# MR26_GSS_8.net
KiCad netlist of a schematic drawn in Altium Designer
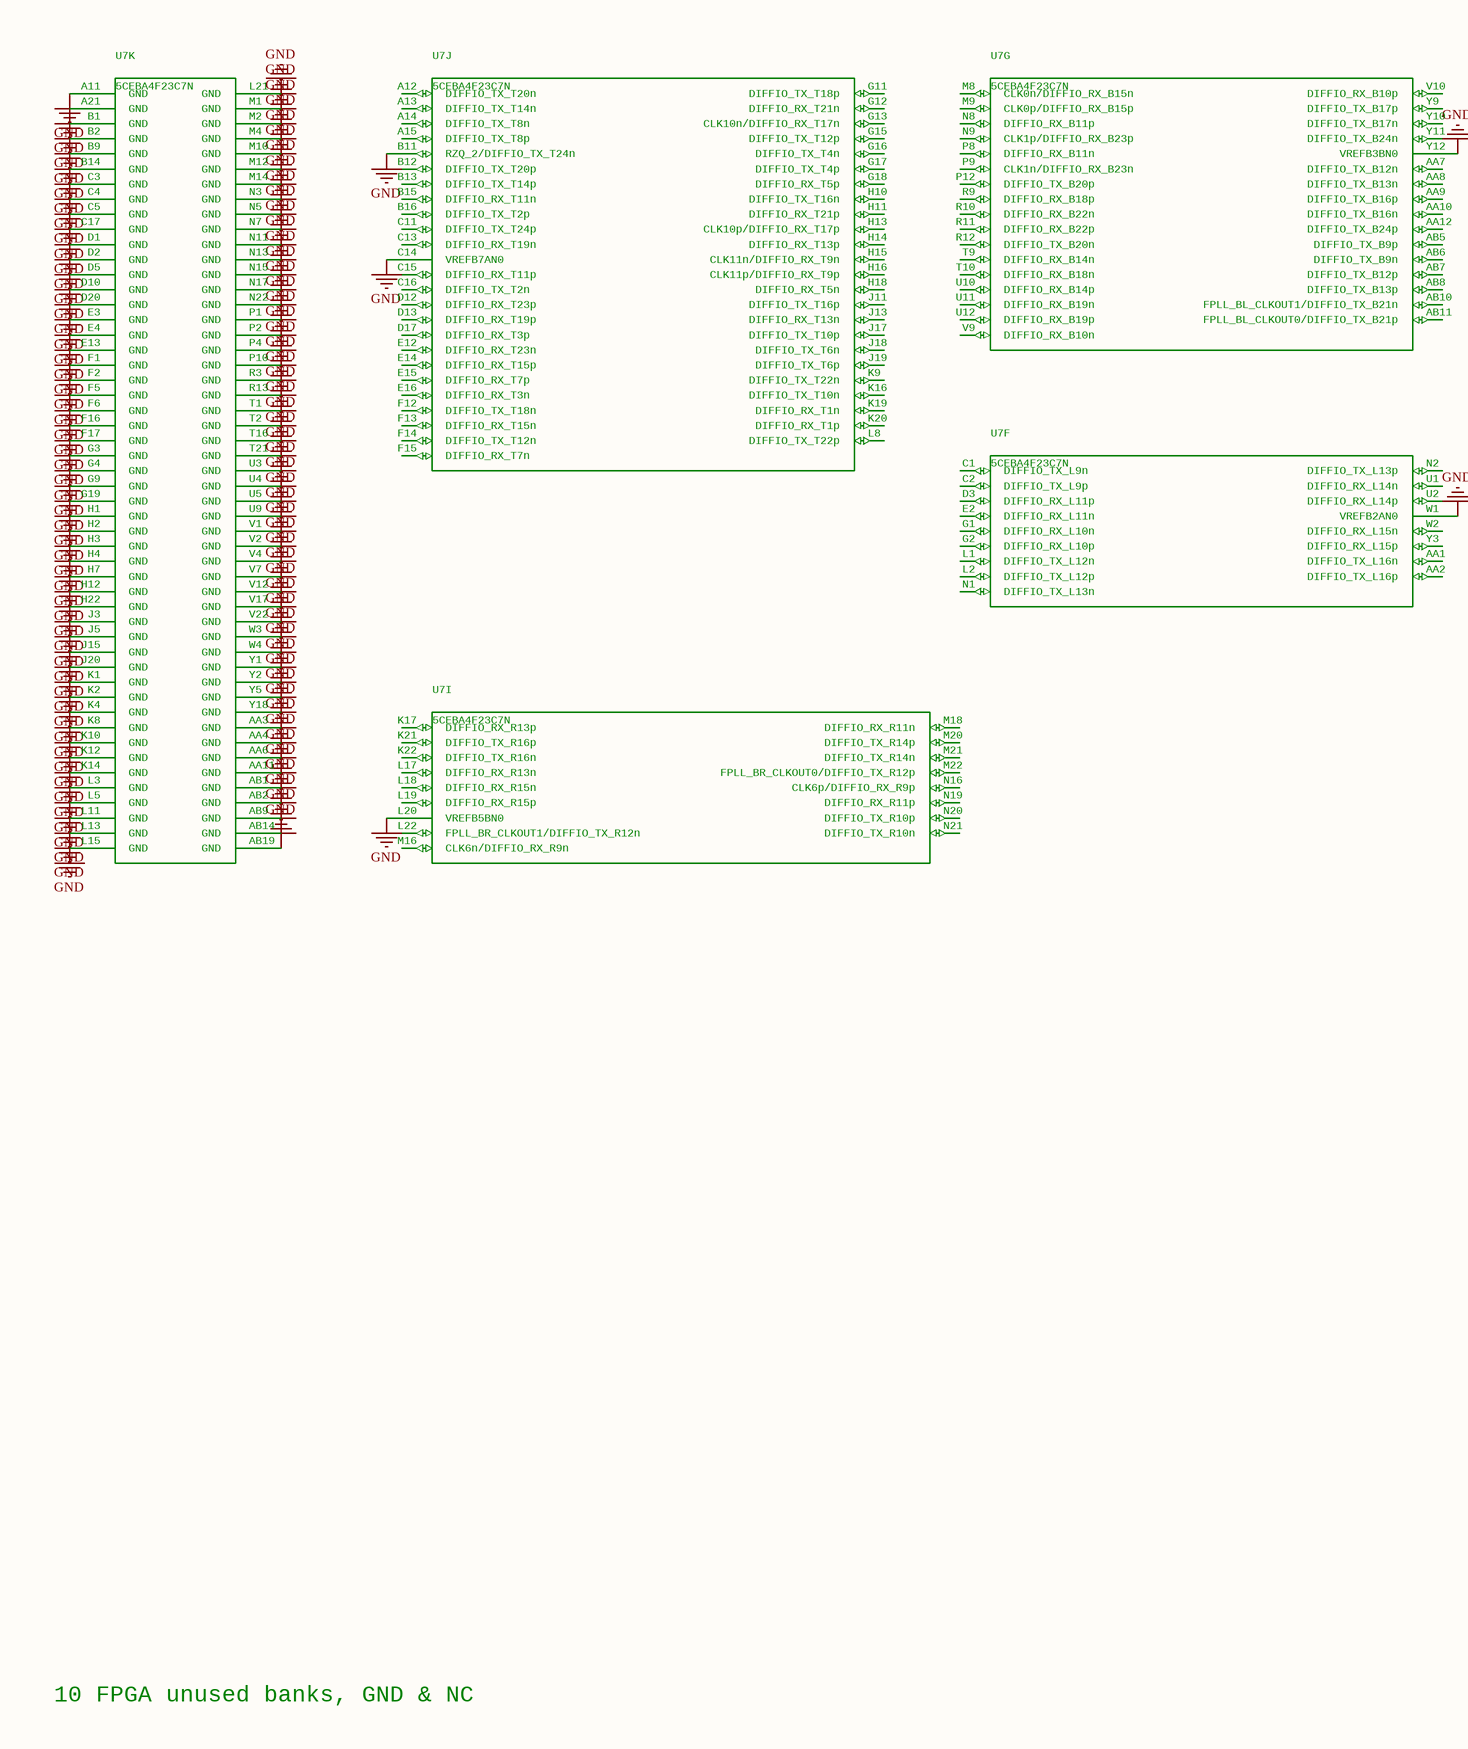
[diagram p0: MR26_GSS_8.SchDoc, left]
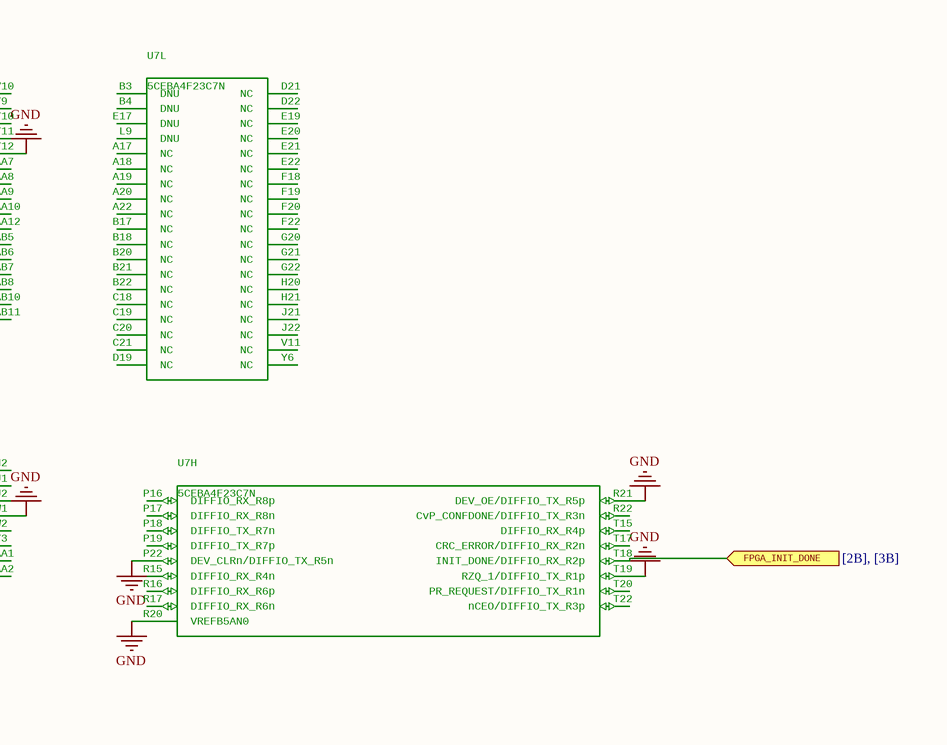
[diagram p1: MR26_GSS_8.SchDoc, right]

(export (version "E")
  (design (tool "Eeschema 10.0.6"))
  (components
    (comp (ref "U7")
      (value "5CEBA4F23C7N")
      (footprint "FBGA-484_23x23_1.0mm")
      (libsource (lib "MR26") (part "5CEBA4F23C7NFBGA-484_23x23_1.0mm"))
    )
  )
  (nets
    (net (code "1") (name "/FPGA_INIT_DONE") (class "Default")
      (node (ref "U7") (pin "T18") (pinfunction "INIT_DONE/DIFFIO_RX_R2p_T18") (pintype "bidirectional"))
    )
    (net (code "2") (name "GND") (class "Default")
      (node (ref "U7") (pin "A11") (pinfunction "GND_A11") (pintype "power_in"))
      (node (ref "U7") (pin "A21") (pinfunction "GND_A21") (pintype "power_in"))
      (node (ref "U7") (pin "AA11") (pinfunction "GND_AA11") (pintype "power_in"))
      (node (ref "U7") (pin "AA3") (pinfunction "GND_AA3") (pintype "power_in"))
      (node (ref "U7") (pin "AA4") (pinfunction "GND_AA4") (pintype "power_in"))
      (node (ref "U7") (pin "AA6") (pinfunction "GND_AA6") (pintype "power_in"))
      (node (ref "U7") (pin "AB1") (pinfunction "GND_AB1") (pintype "power_in"))
      (node (ref "U7") (pin "AB14") (pinfunction "GND_AB14") (pintype "power_in"))
      (node (ref "U7") (pin "AB19") (pinfunction "GND_AB19") (pintype "power_in"))
      (node (ref "U7") (pin "AB2") (pinfunction "GND_AB2") (pintype "power_in"))
      (node (ref "U7") (pin "AB9") (pinfunction "GND_AB9") (pintype "power_in"))
      (node (ref "U7") (pin "B1") (pinfunction "GND_B1") (pintype "power_in"))
      (node (ref "U7") (pin "B11") (pinfunction "RZQ_2/DIFFIO_TX_T24n_B11") (pintype "bidirectional"))
      (node (ref "U7") (pin "B14") (pinfunction "GND_B14") (pintype "power_in"))
      (node (ref "U7") (pin "B2") (pinfunction "GND_B2") (pintype "power_in"))
      (node (ref "U7") (pin "B9") (pinfunction "GND_B9") (pintype "power_in"))
      (node (ref "U7") (pin "C14") (pinfunction "VREFB7AN0_C14") (pintype "power_in"))
      (node (ref "U7") (pin "C17") (pinfunction "GND_C17") (pintype "power_in"))
      (node (ref "U7") (pin "C3") (pinfunction "GND_C3") (pintype "power_in"))
      (node (ref "U7") (pin "C4") (pinfunction "GND_C4") (pintype "power_in"))
      (node (ref "U7") (pin "C5") (pinfunction "GND_C5") (pintype "power_in"))
      (node (ref "U7") (pin "D1") (pinfunction "GND_D1") (pintype "power_in"))
      (node (ref "U7") (pin "D10") (pinfunction "GND_D10") (pintype "power_in"))
      (node (ref "U7") (pin "D2") (pinfunction "GND_D2") (pintype "power_in"))
      (node (ref "U7") (pin "D20") (pinfunction "GND_D20") (pintype "power_in"))
      (node (ref "U7") (pin "D5") (pinfunction "GND_D5") (pintype "power_in"))
      (node (ref "U7") (pin "E13") (pinfunction "GND_E13") (pintype "power_in"))
      (node (ref "U7") (pin "E3") (pinfunction "GND_E3") (pintype "power_in"))
      (node (ref "U7") (pin "E4") (pinfunction "GND_E4") (pintype "power_in"))
      (node (ref "U7") (pin "F1") (pinfunction "GND_F1") (pintype "power_in"))
      (node (ref "U7") (pin "F16") (pinfunction "GND_F16") (pintype "power_in"))
      (node (ref "U7") (pin "F17") (pinfunction "GND_F17") (pintype "power_in"))
      (node (ref "U7") (pin "F2") (pinfunction "GND_F2") (pintype "power_in"))
      (node (ref "U7") (pin "F5") (pinfunction "GND_F5") (pintype "power_in"))
      (node (ref "U7") (pin "F6") (pinfunction "GND_F6") (pintype "power_in"))
      (node (ref "U7") (pin "G19") (pinfunction "GND_G19") (pintype "power_in"))
      (node (ref "U7") (pin "G3") (pinfunction "GND_G3") (pintype "power_in"))
      (node (ref "U7") (pin "G4") (pinfunction "GND_G4") (pintype "power_in"))
      (node (ref "U7") (pin "G9") (pinfunction "GND_G9") (pintype "power_in"))
      (node (ref "U7") (pin "H1") (pinfunction "GND_H1") (pintype "power_in"))
      (node (ref "U7") (pin "H12") (pinfunction "GND_H12") (pintype "power_in"))
      (node (ref "U7") (pin "H2") (pinfunction "GND_H2") (pintype "power_in"))
      (node (ref "U7") (pin "H22") (pinfunction "GND_H22") (pintype "power_in"))
      (node (ref "U7") (pin "H3") (pinfunction "GND_H3") (pintype "power_in"))
      (node (ref "U7") (pin "H4") (pinfunction "GND_H4") (pintype "power_in"))
      (node (ref "U7") (pin "H7") (pinfunction "GND_H7") (pintype "power_in"))
      (node (ref "U7") (pin "J15") (pinfunction "GND_J15") (pintype "power_in"))
      (node (ref "U7") (pin "J20") (pinfunction "GND_J20") (pintype "power_in"))
      (node (ref "U7") (pin "J3") (pinfunction "GND_J3") (pintype "power_in"))
      (node (ref "U7") (pin "J5") (pinfunction "GND_J5") (pintype "power_in"))
      (node (ref "U7") (pin "K1") (pinfunction "GND_K1") (pintype "power_in"))
      (node (ref "U7") (pin "K10") (pinfunction "GND_K10") (pintype "power_in"))
      (node (ref "U7") (pin "K12") (pinfunction "GND_K12") (pintype "power_in"))
      (node (ref "U7") (pin "K14") (pinfunction "GND_K14") (pintype "power_in"))
      (node (ref "U7") (pin "K2") (pinfunction "GND_K2") (pintype "power_in"))
      (node (ref "U7") (pin "K4") (pinfunction "GND_K4") (pintype "power_in"))
      (node (ref "U7") (pin "K8") (pinfunction "GND_K8") (pintype "power_in"))
      (node (ref "U7") (pin "L11") (pinfunction "GND_L11") (pintype "power_in"))
      (node (ref "U7") (pin "L13") (pinfunction "GND_L13") (pintype "power_in"))
      (node (ref "U7") (pin "L15") (pinfunction "GND_L15") (pintype "power_in"))
      (node (ref "U7") (pin "L20") (pinfunction "VREFB5BN0_L20") (pintype "power_in"))
      (node (ref "U7") (pin "L21") (pinfunction "GND_L21") (pintype "power_in"))
      (node (ref "U7") (pin "L3") (pinfunction "GND_L3") (pintype "power_in"))
      (node (ref "U7") (pin "L5") (pinfunction "GND_L5") (pintype "power_in"))
      (node (ref "U7") (pin "M1") (pinfunction "GND_M1") (pintype "power_in"))
      (node (ref "U7") (pin "M10") (pinfunction "GND_M10") (pintype "power_in"))
      (node (ref "U7") (pin "M12") (pinfunction "GND_M12") (pintype "power_in"))
      (node (ref "U7") (pin "M14") (pinfunction "GND_M14") (pintype "power_in"))
      (node (ref "U7") (pin "M2") (pinfunction "GND_M2") (pintype "power_in"))
      (node (ref "U7") (pin "M4") (pinfunction "GND_M4") (pintype "power_in"))
      (node (ref "U7") (pin "N11") (pinfunction "GND_N11") (pintype "power_in"))
      (node (ref "U7") (pin "N13") (pinfunction "GND_N13") (pintype "power_in"))
      (node (ref "U7") (pin "N15") (pinfunction "GND_N15") (pintype "power_in"))
      (node (ref "U7") (pin "N17") (pinfunction "GND_N17") (pintype "power_in"))
      (node (ref "U7") (pin "N22") (pinfunction "GND_N22") (pintype "power_in"))
      (node (ref "U7") (pin "N3") (pinfunction "GND_N3") (pintype "power_in"))
      (node (ref "U7") (pin "N5") (pinfunction "GND_N5") (pintype "power_in"))
      (node (ref "U7") (pin "N7") (pinfunction "GND_N7") (pintype "power_in"))
      (node (ref "U7") (pin "P1") (pinfunction "GND_P1") (pintype "power_in"))
      (node (ref "U7") (pin "P10") (pinfunction "GND_P10") (pintype "power_in"))
      (node (ref "U7") (pin "P2") (pinfunction "GND_P2") (pintype "power_in"))
      (node (ref "U7") (pin "P22") (pinfunction "DEV_CLRn/DIFFIO_TX_R5n_P22") (pintype "bidirectional"))
      (node (ref "U7") (pin "P4") (pinfunction "GND_P4") (pintype "power_in"))
      (node (ref "U7") (pin "R13") (pinfunction "GND_R13") (pintype "power_in"))
      (node (ref "U7") (pin "R20") (pinfunction "VREFB5AN0_R20") (pintype "power_in"))
      (node (ref "U7") (pin "R21") (pinfunction "DEV_OE/DIFFIO_TX_R5p_R21") (pintype "bidirectional"))
      (node (ref "U7") (pin "R3") (pinfunction "GND_R3") (pintype "power_in"))
      (node (ref "U7") (pin "T1") (pinfunction "GND_T1") (pintype "power_in"))
      (node (ref "U7") (pin "T16") (pinfunction "GND_T16") (pintype "power_in"))
      (node (ref "U7") (pin "T19") (pinfunction "RZQ_1/DIFFIO_TX_R1p_T19") (pintype "bidirectional"))
      (node (ref "U7") (pin "T2") (pinfunction "GND_T2") (pintype "power_in"))
      (node (ref "U7") (pin "T21") (pinfunction "GND_T21") (pintype "power_in"))
      (node (ref "U7") (pin "U3") (pinfunction "GND_U3") (pintype "power_in"))
      (node (ref "U7") (pin "U4") (pinfunction "GND_U4") (pintype "power_in"))
      (node (ref "U7") (pin "U5") (pinfunction "GND_U5") (pintype "power_in"))
      (node (ref "U7") (pin "U9") (pinfunction "GND_U9") (pintype "power_in"))
      (node (ref "U7") (pin "V1") (pinfunction "GND_V1") (pintype "power_in"))
      (node (ref "U7") (pin "V12") (pinfunction "GND_V12") (pintype "power_in"))
      (node (ref "U7") (pin "V17") (pinfunction "GND_V17") (pintype "power_in"))
      (node (ref "U7") (pin "V2") (pinfunction "GND_V2") (pintype "power_in"))
      (node (ref "U7") (pin "V22") (pinfunction "GND_V22") (pintype "power_in"))
      (node (ref "U7") (pin "V4") (pinfunction "GND_V4") (pintype "power_in"))
      (node (ref "U7") (pin "V7") (pinfunction "GND_V7") (pintype "power_in"))
      (node (ref "U7") (pin "W1") (pinfunction "VREFB2AN0_W1") (pintype "power_in"))
      (node (ref "U7") (pin "W3") (pinfunction "GND_W3") (pintype "power_in"))
      (node (ref "U7") (pin "W4") (pinfunction "GND_W4") (pintype "power_in"))
      (node (ref "U7") (pin "Y1") (pinfunction "GND_Y1") (pintype "power_in"))
      (node (ref "U7") (pin "Y12") (pinfunction "VREFB3BN0_Y12") (pintype "power_in"))
      (node (ref "U7") (pin "Y18") (pinfunction "GND_Y18") (pintype "power_in"))
      (node (ref "U7") (pin "Y2") (pinfunction "GND_Y2") (pintype "power_in"))
      (node (ref "U7") (pin "Y5") (pinfunction "GND_Y5") (pintype "power_in"))
    )
    (net (code "3") (name "unconnected-(U7F-DIFFIO_RX_L10n-PadG1)") (class "Default")
      (node (ref "U7") (pin "G1") (pinfunction "DIFFIO_RX_L10n_G1") (pintype "bidirectional"))
    )
    (net (code "4") (name "unconnected-(U7F-DIFFIO_RX_L10p-PadG2)") (class "Default")
      (node (ref "U7") (pin "G2") (pinfunction "DIFFIO_RX_L10p_G2") (pintype "bidirectional"))
    )
    (net (code "5") (name "unconnected-(U7F-DIFFIO_RX_L11n-PadE2)") (class "Default")
      (node (ref "U7") (pin "E2") (pinfunction "DIFFIO_RX_L11n_E2") (pintype "bidirectional"))
    )
    (net (code "6") (name "unconnected-(U7F-DIFFIO_RX_L11p-PadD3)") (class "Default")
      (node (ref "U7") (pin "D3") (pinfunction "DIFFIO_RX_L11p_D3") (pintype "bidirectional"))
    )
    (net (code "7") (name "unconnected-(U7F-DIFFIO_RX_L14n-PadU1)") (class "Default")
      (node (ref "U7") (pin "U1") (pinfunction "DIFFIO_RX_L14n_U1") (pintype "bidirectional"))
    )
    (net (code "8") (name "unconnected-(U7F-DIFFIO_RX_L14p-PadU2)") (class "Default")
      (node (ref "U7") (pin "U2") (pinfunction "DIFFIO_RX_L14p_U2") (pintype "bidirectional"))
    )
    (net (code "9") (name "unconnected-(U7F-DIFFIO_RX_L15n-PadW2)") (class "Default")
      (node (ref "U7") (pin "W2") (pinfunction "DIFFIO_RX_L15n_W2") (pintype "bidirectional"))
    )
    (net (code "10") (name "unconnected-(U7F-DIFFIO_RX_L15p-PadY3)") (class "Default")
      (node (ref "U7") (pin "Y3") (pinfunction "DIFFIO_RX_L15p_Y3") (pintype "bidirectional"))
    )
    (net (code "11") (name "unconnected-(U7F-DIFFIO_TX_L9n-PadC1)") (class "Default")
      (node (ref "U7") (pin "C1") (pinfunction "DIFFIO_TX_L9n_C1") (pintype "bidirectional"))
    )
    (net (code "12") (name "unconnected-(U7F-DIFFIO_TX_L9p-PadC2)") (class "Default")
      (node (ref "U7") (pin "C2") (pinfunction "DIFFIO_TX_L9p_C2") (pintype "bidirectional"))
    )
    (net (code "13") (name "unconnected-(U7F-DIFFIO_TX_L12n-PadL1)") (class "Default")
      (node (ref "U7") (pin "L1") (pinfunction "DIFFIO_TX_L12n_L1") (pintype "bidirectional"))
    )
    (net (code "14") (name "unconnected-(U7F-DIFFIO_TX_L12p-PadL2)") (class "Default")
      (node (ref "U7") (pin "L2") (pinfunction "DIFFIO_TX_L12p_L2") (pintype "bidirectional"))
    )
    (net (code "15") (name "unconnected-(U7F-DIFFIO_TX_L13n-PadN1)") (class "Default")
      (node (ref "U7") (pin "N1") (pinfunction "DIFFIO_TX_L13n_N1") (pintype "bidirectional"))
    )
    (net (code "16") (name "unconnected-(U7F-DIFFIO_TX_L13p-PadN2)") (class "Default")
      (node (ref "U7") (pin "N2") (pinfunction "DIFFIO_TX_L13p_N2") (pintype "bidirectional"))
    )
    (net (code "17") (name "unconnected-(U7F-DIFFIO_TX_L16n-PadAA1)") (class "Default")
      (node (ref "U7") (pin "AA1") (pinfunction "DIFFIO_TX_L16n_AA1") (pintype "bidirectional"))
    )
    (net (code "18") (name "unconnected-(U7F-DIFFIO_TX_L16p-PadAA2)") (class "Default")
      (node (ref "U7") (pin "AA2") (pinfunction "DIFFIO_TX_L16p_AA2") (pintype "bidirectional"))
    )
    (net (code "19") (name "unconnected-(U7G-CLK0n{slash}DIFFIO_RX_B15n-PadM8)") (class "Default")
      (node (ref "U7") (pin "M8") (pinfunction "CLK0n/DIFFIO_RX_B15n_M8") (pintype "bidirectional"))
    )
    (net (code "20") (name "unconnected-(U7G-CLK0p{slash}DIFFIO_RX_B15p-PadM9)") (class "Default")
      (node (ref "U7") (pin "M9") (pinfunction "CLK0p/DIFFIO_RX_B15p_M9") (pintype "bidirectional"))
    )
    (net (code "21") (name "unconnected-(U7G-CLK1n{slash}DIFFIO_RX_B23n-PadP9)") (class "Default")
      (node (ref "U7") (pin "P9") (pinfunction "CLK1n/DIFFIO_RX_B23n_P9") (pintype "bidirectional"))
    )
    (net (code "22") (name "unconnected-(U7G-CLK1p{slash}DIFFIO_RX_B23p-PadN9)") (class "Default")
      (node (ref "U7") (pin "N9") (pinfunction "CLK1p/DIFFIO_RX_B23p_N9") (pintype "bidirectional"))
    )
    (net (code "23") (name "unconnected-(U7G-DIFFIO_RX_B10n-PadV9)") (class "Default")
      (node (ref "U7") (pin "V9") (pinfunction "DIFFIO_RX_B10n_V9") (pintype "bidirectional"))
    )
    (net (code "24") (name "unconnected-(U7G-DIFFIO_RX_B10p-PadV10)") (class "Default")
      (node (ref "U7") (pin "V10") (pinfunction "DIFFIO_RX_B10p_V10") (pintype "bidirectional"))
    )
    (net (code "25") (name "unconnected-(U7G-DIFFIO_RX_B11n-PadP8)") (class "Default")
      (node (ref "U7") (pin "P8") (pinfunction "DIFFIO_RX_B11n_P8") (pintype "bidirectional"))
    )
    (net (code "26") (name "unconnected-(U7G-DIFFIO_RX_B11p-PadN8)") (class "Default")
      (node (ref "U7") (pin "N8") (pinfunction "DIFFIO_RX_B11p_N8") (pintype "bidirectional"))
    )
    (net (code "27") (name "unconnected-(U7G-DIFFIO_RX_B14n-PadT9)") (class "Default")
      (node (ref "U7") (pin "T9") (pinfunction "DIFFIO_RX_B14n_T9") (pintype "bidirectional"))
    )
    (net (code "28") (name "unconnected-(U7G-DIFFIO_RX_B14p-PadU10)") (class "Default")
      (node (ref "U7") (pin "U10") (pinfunction "DIFFIO_RX_B14p_U10") (pintype "bidirectional"))
    )
    (net (code "29") (name "unconnected-(U7G-DIFFIO_RX_B18n-PadT10)") (class "Default")
      (node (ref "U7") (pin "T10") (pinfunction "DIFFIO_RX_B18n_T10") (pintype "bidirectional"))
    )
    (net (code "30") (name "unconnected-(U7G-DIFFIO_RX_B18p-PadR9)") (class "Default")
      (node (ref "U7") (pin "R9") (pinfunction "DIFFIO_RX_B18p_R9") (pintype "bidirectional"))
    )
    (net (code "31") (name "unconnected-(U7G-DIFFIO_RX_B19n-PadU11)") (class "Default")
      (node (ref "U7") (pin "U11") (pinfunction "DIFFIO_RX_B19n_U11") (pintype "bidirectional"))
    )
    (net (code "32") (name "unconnected-(U7G-DIFFIO_RX_B19p-PadU12)") (class "Default")
      (node (ref "U7") (pin "U12") (pinfunction "DIFFIO_RX_B19p_U12") (pintype "bidirectional"))
    )
    (net (code "33") (name "unconnected-(U7G-DIFFIO_RX_B22n-PadR10)") (class "Default")
      (node (ref "U7") (pin "R10") (pinfunction "DIFFIO_RX_B22n_R10") (pintype "bidirectional"))
    )
    (net (code "34") (name "unconnected-(U7G-DIFFIO_RX_B22p-PadR11)") (class "Default")
      (node (ref "U7") (pin "R11") (pinfunction "DIFFIO_RX_B22p_R11") (pintype "bidirectional"))
    )
    (net (code "35") (name "unconnected-(U7G-DIFFIO_TX_B9n-PadAB6)") (class "Default")
      (node (ref "U7") (pin "AB6") (pinfunction "DIFFIO_TX_B9n_AB6") (pintype "bidirectional"))
    )
    (net (code "36") (name "unconnected-(U7G-DIFFIO_TX_B9p-PadAB5)") (class "Default")
      (node (ref "U7") (pin "AB5") (pinfunction "DIFFIO_TX_B9p_AB5") (pintype "bidirectional"))
    )
    (net (code "37") (name "unconnected-(U7G-DIFFIO_TX_B12n-PadAA7)") (class "Default")
      (node (ref "U7") (pin "AA7") (pinfunction "DIFFIO_TX_B12n_AA7") (pintype "bidirectional"))
    )
    (net (code "38") (name "unconnected-(U7G-DIFFIO_TX_B12p-PadAB7)") (class "Default")
      (node (ref "U7") (pin "AB7") (pinfunction "DIFFIO_TX_B12p_AB7") (pintype "bidirectional"))
    )
    (net (code "39") (name "unconnected-(U7G-DIFFIO_TX_B13n-PadAA8)") (class "Default")
      (node (ref "U7") (pin "AA8") (pinfunction "DIFFIO_TX_B13n_AA8") (pintype "bidirectional"))
    )
    (net (code "40") (name "unconnected-(U7G-DIFFIO_TX_B13p-PadAB8)") (class "Default")
      (node (ref "U7") (pin "AB8") (pinfunction "DIFFIO_TX_B13p_AB8") (pintype "bidirectional"))
    )
    (net (code "41") (name "unconnected-(U7G-DIFFIO_TX_B16n-PadAA10)") (class "Default")
      (node (ref "U7") (pin "AA10") (pinfunction "DIFFIO_TX_B16n_AA10") (pintype "bidirectional"))
    )
    (net (code "42") (name "unconnected-(U7G-DIFFIO_TX_B16p-PadAA9)") (class "Default")
      (node (ref "U7") (pin "AA9") (pinfunction "DIFFIO_TX_B16p_AA9") (pintype "bidirectional"))
    )
    (net (code "43") (name "unconnected-(U7G-DIFFIO_TX_B17n-PadY10)") (class "Default")
      (node (ref "U7") (pin "Y10") (pinfunction "DIFFIO_TX_B17n_Y10") (pintype "bidirectional"))
    )
    (net (code "44") (name "unconnected-(U7G-DIFFIO_TX_B17p-PadY9)") (class "Default")
      (node (ref "U7") (pin "Y9") (pinfunction "DIFFIO_TX_B17p_Y9") (pintype "bidirectional"))
    )
    (net (code "45") (name "unconnected-(U7G-DIFFIO_TX_B20n-PadR12)") (class "Default")
      (node (ref "U7") (pin "R12") (pinfunction "DIFFIO_TX_B20n_R12") (pintype "bidirectional"))
    )
    (net (code "46") (name "unconnected-(U7G-DIFFIO_TX_B20p-PadP12)") (class "Default")
      (node (ref "U7") (pin "P12") (pinfunction "DIFFIO_TX_B20p_P12") (pintype "bidirectional"))
    )
    (net (code "47") (name "unconnected-(U7G-DIFFIO_TX_B24n-PadY11)") (class "Default")
      (node (ref "U7") (pin "Y11") (pinfunction "DIFFIO_TX_B24n_Y11") (pintype "bidirectional"))
    )
    (net (code "48") (name "unconnected-(U7G-DIFFIO_TX_B24p-PadAA12)") (class "Default")
      (node (ref "U7") (pin "AA12") (pinfunction "DIFFIO_TX_B24p_AA12") (pintype "bidirectional"))
    )
    (net (code "49") (name "unconnected-(U7G-FPLL_BL_CLKOUT0{slash}DIFFIO_TX_B21p-PadAB11)") (class "Default")
      (node (ref "U7") (pin "AB11") (pinfunction "FPLL_BL_CLKOUT0/DIFFIO_TX_B21p_AB11") (pintype "bidirectional"))
    )
    (net (code "50") (name "unconnected-(U7G-FPLL_BL_CLKOUT1{slash}DIFFIO_TX_B21n-PadAB10)") (class "Default")
      (node (ref "U7") (pin "AB10") (pinfunction "FPLL_BL_CLKOUT1/DIFFIO_TX_B21n_AB10") (pintype "bidirectional"))
    )
    (net (code "51") (name "unconnected-(U7H-CRC_ERROR{slash}DIFFIO_RX_R2n-PadT17)") (class "Default")
      (node (ref "U7") (pin "T17") (pinfunction "CRC_ERROR/DIFFIO_RX_R2n_T17") (pintype "bidirectional"))
    )
    (net (code "52") (name "unconnected-(U7H-CvP_CONFDONE{slash}DIFFIO_TX_R3n-PadR22)") (class "Default")
      (node (ref "U7") (pin "R22") (pinfunction "CvP_CONFDONE/DIFFIO_TX_R3n_R22") (pintype "bidirectional"))
    )
    (net (code "53") (name "unconnected-(U7H-DIFFIO_RX_R4n-PadR15)") (class "Default")
      (node (ref "U7") (pin "R15") (pinfunction "DIFFIO_RX_R4n_R15") (pintype "bidirectional"))
    )
    (net (code "54") (name "unconnected-(U7H-DIFFIO_RX_R4p-PadT15)") (class "Default")
      (node (ref "U7") (pin "T15") (pinfunction "DIFFIO_RX_R4p_T15") (pintype "bidirectional"))
    )
    (net (code "55") (name "unconnected-(U7H-DIFFIO_RX_R6n-PadR17)") (class "Default")
      (node (ref "U7") (pin "R17") (pinfunction "DIFFIO_RX_R6n_R17") (pintype "bidirectional"))
    )
    (net (code "56") (name "unconnected-(U7H-DIFFIO_RX_R6p-PadR16)") (class "Default")
      (node (ref "U7") (pin "R16") (pinfunction "DIFFIO_RX_R6p_R16") (pintype "bidirectional"))
    )
    (net (code "57") (name "unconnected-(U7H-DIFFIO_RX_R8n-PadP17)") (class "Default")
      (node (ref "U7") (pin "P17") (pinfunction "DIFFIO_RX_R8n_P17") (pintype "bidirectional"))
    )
    (net (code "58") (name "unconnected-(U7H-DIFFIO_RX_R8p-PadP16)") (class "Default")
      (node (ref "U7") (pin "P16") (pinfunction "DIFFIO_RX_R8p_P16") (pintype "bidirectional"))
    )
    (net (code "59") (name "unconnected-(U7H-DIFFIO_TX_R7n-PadP18)") (class "Default")
      (node (ref "U7") (pin "P18") (pinfunction "DIFFIO_TX_R7n_P18") (pintype "bidirectional"))
    )
    (net (code "60") (name "unconnected-(U7H-DIFFIO_TX_R7p-PadP19)") (class "Default")
      (node (ref "U7") (pin "P19") (pinfunction "DIFFIO_TX_R7p_P19") (pintype "bidirectional"))
    )
    (net (code "61") (name "unconnected-(U7H-PR_REQUEST{slash}DIFFIO_TX_R1n-PadT20)") (class "Default")
      (node (ref "U7") (pin "T20") (pinfunction "PR_REQUEST/DIFFIO_TX_R1n_T20") (pintype "bidirectional"))
    )
    (net (code "62") (name "unconnected-(U7H-nCEO{slash}DIFFIO_TX_R3p-PadT22)") (class "Default")
      (node (ref "U7") (pin "T22") (pinfunction "nCEO/DIFFIO_TX_R3p_T22") (pintype "bidirectional"))
    )
    (net (code "63") (name "unconnected-(U7I-CLK6n{slash}DIFFIO_RX_R9n-PadM16)") (class "Default")
      (node (ref "U7") (pin "M16") (pinfunction "CLK6n/DIFFIO_RX_R9n_M16") (pintype "bidirectional"))
    )
    (net (code "64") (name "unconnected-(U7I-CLK6p{slash}DIFFIO_RX_R9p-PadN16)") (class "Default")
      (node (ref "U7") (pin "N16") (pinfunction "CLK6p/DIFFIO_RX_R9p_N16") (pintype "bidirectional"))
    )
    (net (code "65") (name "unconnected-(U7I-DIFFIO_RX_R11n-PadM18)") (class "Default")
      (node (ref "U7") (pin "M18") (pinfunction "DIFFIO_RX_R11n_M18") (pintype "bidirectional"))
    )
    (net (code "66") (name "unconnected-(U7I-DIFFIO_RX_R11p-PadN19)") (class "Default")
      (node (ref "U7") (pin "N19") (pinfunction "DIFFIO_RX_R11p_N19") (pintype "bidirectional"))
    )
    (net (code "67") (name "unconnected-(U7I-DIFFIO_RX_R13n-PadL17)") (class "Default")
      (node (ref "U7") (pin "L17") (pinfunction "DIFFIO_RX_R13n_L17") (pintype "bidirectional"))
    )
    (net (code "68") (name "unconnected-(U7I-DIFFIO_RX_R13p-PadK17)") (class "Default")
      (node (ref "U7") (pin "K17") (pinfunction "DIFFIO_RX_R13p_K17") (pintype "bidirectional"))
    )
    (net (code "69") (name "unconnected-(U7I-DIFFIO_RX_R15n-PadL18)") (class "Default")
      (node (ref "U7") (pin "L18") (pinfunction "DIFFIO_RX_R15n_L18") (pintype "bidirectional"))
    )
    (net (code "70") (name "unconnected-(U7I-DIFFIO_RX_R15p-PadL19)") (class "Default")
      (node (ref "U7") (pin "L19") (pinfunction "DIFFIO_RX_R15p_L19") (pintype "bidirectional"))
    )
    (net (code "71") (name "unconnected-(U7I-DIFFIO_TX_R10n-PadN21)") (class "Default")
      (node (ref "U7") (pin "N21") (pinfunction "DIFFIO_TX_R10n_N21") (pintype "bidirectional"))
    )
    (net (code "72") (name "unconnected-(U7I-DIFFIO_TX_R10p-PadN20)") (class "Default")
      (node (ref "U7") (pin "N20") (pinfunction "DIFFIO_TX_R10p_N20") (pintype "bidirectional"))
    )
    (net (code "73") (name "unconnected-(U7I-DIFFIO_TX_R14n-PadM21)") (class "Default")
      (node (ref "U7") (pin "M21") (pinfunction "DIFFIO_TX_R14n_M21") (pintype "bidirectional"))
    )
    (net (code "74") (name "unconnected-(U7I-DIFFIO_TX_R14p-PadM20)") (class "Default")
      (node (ref "U7") (pin "M20") (pinfunction "DIFFIO_TX_R14p_M20") (pintype "bidirectional"))
    )
    (net (code "75") (name "unconnected-(U7I-DIFFIO_TX_R16n-PadK22)") (class "Default")
      (node (ref "U7") (pin "K22") (pinfunction "DIFFIO_TX_R16n_K22") (pintype "bidirectional"))
    )
    (net (code "76") (name "unconnected-(U7I-DIFFIO_TX_R16p-PadK21)") (class "Default")
      (node (ref "U7") (pin "K21") (pinfunction "DIFFIO_TX_R16p_K21") (pintype "bidirectional"))
    )
    (net (code "77") (name "unconnected-(U7I-FPLL_BR_CLKOUT0{slash}DIFFIO_TX_R12p-PadM22)") (class "Default")
      (node (ref "U7") (pin "M22") (pinfunction "FPLL_BR_CLKOUT0/DIFFIO_TX_R12p_M22") (pintype "bidirectional"))
    )
    (net (code "78") (name "unconnected-(U7I-FPLL_BR_CLKOUT1{slash}DIFFIO_TX_R12n-PadL22)") (class "Default")
      (node (ref "U7") (pin "L22") (pinfunction "FPLL_BR_CLKOUT1/DIFFIO_TX_R12n_L22") (pintype "bidirectional"))
    )
    (net (code "79") (name "unconnected-(U7J-CLK10n{slash}DIFFIO_RX_T17n-PadG13)") (class "Default")
      (node (ref "U7") (pin "G13") (pinfunction "CLK10n/DIFFIO_RX_T17n_G13") (pintype "bidirectional"))
    )
    (net (code "80") (name "unconnected-(U7J-CLK10p{slash}DIFFIO_RX_T17p-PadH13)") (class "Default")
      (node (ref "U7") (pin "H13") (pinfunction "CLK10p/DIFFIO_RX_T17p_H13") (pintype "bidirectional"))
    )
    (net (code "81") (name "unconnected-(U7J-CLK11n{slash}DIFFIO_RX_T9n-PadH15)") (class "Default")
      (node (ref "U7") (pin "H15") (pinfunction "CLK11n/DIFFIO_RX_T9n_H15") (pintype "bidirectional"))
    )
    (net (code "82") (name "unconnected-(U7J-CLK11p{slash}DIFFIO_RX_T9p-PadH16)") (class "Default")
      (node (ref "U7") (pin "H16") (pinfunction "CLK11p/DIFFIO_RX_T9p_H16") (pintype "bidirectional"))
    )
    (net (code "83") (name "unconnected-(U7J-DIFFIO_RX_T1n-PadK19)") (class "Default")
      (node (ref "U7") (pin "K19") (pinfunction "DIFFIO_RX_T1n_K19") (pintype "bidirectional"))
    )
    (net (code "84") (name "unconnected-(U7J-DIFFIO_RX_T1p-PadK20)") (class "Default")
      (node (ref "U7") (pin "K20") (pinfunction "DIFFIO_RX_T1p_K20") (pintype "bidirectional"))
    )
    (net (code "85") (name "unconnected-(U7J-DIFFIO_RX_T3n-PadE16)") (class "Default")
      (node (ref "U7") (pin "E16") (pinfunction "DIFFIO_RX_T3n_E16") (pintype "bidirectional"))
    )
    (net (code "86") (name "unconnected-(U7J-DIFFIO_RX_T3p-PadD17)") (class "Default")
      (node (ref "U7") (pin "D17") (pinfunction "DIFFIO_RX_T3p_D17") (pintype "bidirectional"))
    )
    (net (code "87") (name "unconnected-(U7J-DIFFIO_RX_T5n-PadH18)") (class "Default")
      (node (ref "U7") (pin "H18") (pinfunction "DIFFIO_RX_T5n_H18") (pintype "bidirectional"))
    )
    (net (code "88") (name "unconnected-(U7J-DIFFIO_RX_T5p-PadG18)") (class "Default")
      (node (ref "U7") (pin "G18") (pinfunction "DIFFIO_RX_T5p_G18") (pintype "bidirectional"))
    )
    (net (code "89") (name "unconnected-(U7J-DIFFIO_RX_T7n-PadF15)") (class "Default")
      (node (ref "U7") (pin "F15") (pinfunction "DIFFIO_RX_T7n_F15") (pintype "bidirectional"))
    )
    (net (code "90") (name "unconnected-(U7J-DIFFIO_RX_T7p-PadE15)") (class "Default")
      (node (ref "U7") (pin "E15") (pinfunction "DIFFIO_RX_T7p_E15") (pintype "bidirectional"))
    )
    (net (code "91") (name "unconnected-(U7J-DIFFIO_RX_T11n-PadB15)") (class "Default")
      (node (ref "U7") (pin "B15") (pinfunction "DIFFIO_RX_T11n_B15") (pintype "bidirectional"))
    )
    (net (code "92") (name "unconnected-(U7J-DIFFIO_RX_T11p-PadC15)") (class "Default")
      (node (ref "U7") (pin "C15") (pinfunction "DIFFIO_RX_T11p_C15") (pintype "bidirectional"))
    )
    (net (code "93") (name "unconnected-(U7J-DIFFIO_RX_T13n-PadJ13)") (class "Default")
      (node (ref "U7") (pin "J13") (pinfunction "DIFFIO_RX_T13n_J13") (pintype "bidirectional"))
    )
    (net (code "94") (name "unconnected-(U7J-DIFFIO_RX_T13p-PadH14)") (class "Default")
      (node (ref "U7") (pin "H14") (pinfunction "DIFFIO_RX_T13p_H14") (pintype "bidirectional"))
    )
    (net (code "95") (name "unconnected-(U7J-DIFFIO_RX_T15n-PadF13)") (class "Default")
      (node (ref "U7") (pin "F13") (pinfunction "DIFFIO_RX_T15n_F13") (pintype "bidirectional"))
    )
    (net (code "96") (name "unconnected-(U7J-DIFFIO_RX_T15p-PadE14)") (class "Default")
      (node (ref "U7") (pin "E14") (pinfunction "DIFFIO_RX_T15p_E14") (pintype "bidirectional"))
    )
    (net (code "97") (name "unconnected-(U7J-DIFFIO_RX_T19n-PadC13)") (class "Default")
      (node (ref "U7") (pin "C13") (pinfunction "DIFFIO_RX_T19n_C13") (pintype "bidirectional"))
    )
    (net (code "98") (name "unconnected-(U7J-DIFFIO_RX_T19p-PadD13)") (class "Default")
      (node (ref "U7") (pin "D13") (pinfunction "DIFFIO_RX_T19p_D13") (pintype "bidirectional"))
    )
    (net (code "99") (name "unconnected-(U7J-DIFFIO_RX_T21n-PadG12)") (class "Default")
      (node (ref "U7") (pin "G12") (pinfunction "DIFFIO_RX_T21n_G12") (pintype "bidirectional"))
    )
    (net (code "100") (name "unconnected-(U7J-DIFFIO_RX_T21p-PadH11)") (class "Default")
      (node (ref "U7") (pin "H11") (pinfunction "DIFFIO_RX_T21p_H11") (pintype "bidirectional"))
    )
    (net (code "101") (name "unconnected-(U7J-DIFFIO_RX_T23n-PadE12)") (class "Default")
      (node (ref "U7") (pin "E12") (pinfunction "DIFFIO_RX_T23n_E12") (pintype "bidirectional"))
    )
    (net (code "102") (name "unconnected-(U7J-DIFFIO_RX_T23p-PadD12)") (class "Default")
      (node (ref "U7") (pin "D12") (pinfunction "DIFFIO_RX_T23p_D12") (pintype "bidirectional"))
    )
    (net (code "103") (name "unconnected-(U7J-DIFFIO_TX_T2n-PadC16)") (class "Default")
      (node (ref "U7") (pin "C16") (pinfunction "DIFFIO_TX_T2n_C16") (pintype "bidirectional"))
    )
    (net (code "104") (name "unconnected-(U7J-DIFFIO_TX_T2p-PadB16)") (class "Default")
      (node (ref "U7") (pin "B16") (pinfunction "DIFFIO_TX_T2p_B16") (pintype "bidirectional"))
    )
    (net (code "105") (name "unconnected-(U7J-DIFFIO_TX_T4n-PadG16)") (class "Default")
      (node (ref "U7") (pin "G16") (pinfunction "DIFFIO_TX_T4n_G16") (pintype "bidirectional"))
    )
    (net (code "106") (name "unconnected-(U7J-DIFFIO_TX_T4p-PadG17)") (class "Default")
      (node (ref "U7") (pin "G17") (pinfunction "DIFFIO_TX_T4p_G17") (pintype "bidirectional"))
    )
    (net (code "107") (name "unconnected-(U7J-DIFFIO_TX_T6n-PadJ18)") (class "Default")
      (node (ref "U7") (pin "J18") (pinfunction "DIFFIO_TX_T6n_J18") (pintype "bidirectional"))
    )
    (net (code "108") (name "unconnected-(U7J-DIFFIO_TX_T6p-PadJ19)") (class "Default")
      (node (ref "U7") (pin "J19") (pinfunction "DIFFIO_TX_T6p_J19") (pintype "bidirectional"))
    )
    (net (code "109") (name "unconnected-(U7J-DIFFIO_TX_T8n-PadA14)") (class "Default")
      (node (ref "U7") (pin "A14") (pinfunction "DIFFIO_TX_T8n_A14") (pintype "bidirectional"))
    )
    (net (code "110") (name "unconnected-(U7J-DIFFIO_TX_T8p-PadA15)") (class "Default")
      (node (ref "U7") (pin "A15") (pinfunction "DIFFIO_TX_T8p_A15") (pintype "bidirectional"))
    )
    (net (code "111") (name "unconnected-(U7J-DIFFIO_TX_T10n-PadK16)") (class "Default")
      (node (ref "U7") (pin "K16") (pinfunction "DIFFIO_TX_T10n_K16") (pintype "bidirectional"))
    )
    (net (code "112") (name "unconnected-(U7J-DIFFIO_TX_T10p-PadJ17)") (class "Default")
      (node (ref "U7") (pin "J17") (pinfunction "DIFFIO_TX_T10p_J17") (pintype "bidirectional"))
    )
    (net (code "113") (name "unconnected-(U7J-DIFFIO_TX_T12n-PadF14)") (class "Default")
      (node (ref "U7") (pin "F14") (pinfunction "DIFFIO_TX_T12n_F14") (pintype "bidirectional"))
    )
    (net (code "114") (name "unconnected-(U7J-DIFFIO_TX_T12p-PadG15)") (class "Default")
      (node (ref "U7") (pin "G15") (pinfunction "DIFFIO_TX_T12p_G15") (pintype "bidirectional"))
    )
    (net (code "115") (name "unconnected-(U7J-DIFFIO_TX_T14n-PadA13)") (class "Default")
      (node (ref "U7") (pin "A13") (pinfunction "DIFFIO_TX_T14n_A13") (pintype "bidirectional"))
    )
    (net (code "116") (name "unconnected-(U7J-DIFFIO_TX_T14p-PadB13)") (class "Default")
      (node (ref "U7") (pin "B13") (pinfunction "DIFFIO_TX_T14p_B13") (pintype "bidirectional"))
    )
    (net (code "117") (name "unconnected-(U7J-DIFFIO_TX_T16n-PadH10)") (class "Default")
      (node (ref "U7") (pin "H10") (pinfunction "DIFFIO_TX_T16n_H10") (pintype "bidirectional"))
    )
    (net (code "118") (name "unconnected-(U7J-DIFFIO_TX_T16p-PadJ11)") (class "Default")
      (node (ref "U7") (pin "J11") (pinfunction "DIFFIO_TX_T16p_J11") (pintype "bidirectional"))
    )
    (net (code "119") (name "unconnected-(U7J-DIFFIO_TX_T18n-PadF12)") (class "Default")
      (node (ref "U7") (pin "F12") (pinfunction "DIFFIO_TX_T18n_F12") (pintype "bidirectional"))
    )
    (net (code "120") (name "unconnected-(U7J-DIFFIO_TX_T18p-PadG11)") (class "Default")
      (node (ref "U7") (pin "G11") (pinfunction "DIFFIO_TX_T18p_G11") (pintype "bidirectional"))
    )
    (net (code "121") (name "unconnected-(U7J-DIFFIO_TX_T20n-PadA12)") (class "Default")
      (node (ref "U7") (pin "A12") (pinfunction "DIFFIO_TX_T20n_A12") (pintype "bidirectional"))
    )
    (net (code "122") (name "unconnected-(U7J-DIFFIO_TX_T20p-PadB12)") (class "Default")
      (node (ref "U7") (pin "B12") (pinfunction "DIFFIO_TX_T20p_B12") (pintype "bidirectional"))
    )
    (net (code "123") (name "unconnected-(U7J-DIFFIO_TX_T22n-PadK9)") (class "Default")
      (node (ref "U7") (pin "K9") (pinfunction "DIFFIO_TX_T22n_K9") (pintype "bidirectional"))
    )
    (net (code "124") (name "unconnected-(U7J-DIFFIO_TX_T22p-PadL8)") (class "Default")
      (node (ref "U7") (pin "L8") (pinfunction "DIFFIO_TX_T22p_L8") (pintype "bidirectional"))
    )
    (net (code "125") (name "unconnected-(U7J-DIFFIO_TX_T24p-PadC11)") (class "Default")
      (node (ref "U7") (pin "C11") (pinfunction "DIFFIO_TX_T24p_C11") (pintype "bidirectional"))
    )
    (net (code "126") (name "unconnected-(U7L-DNU-PadB3)") (class "Default")
      (node (ref "U7") (pin "B3") (pinfunction "DNU_B3") (pintype "passive"))
    )
    (net (code "127") (name "unconnected-(U7L-DNU-PadB4)") (class "Default")
      (node (ref "U7") (pin "B4") (pinfunction "DNU_B4") (pintype "passive"))
    )
    (net (code "128") (name "unconnected-(U7L-DNU-PadE17)") (class "Default")
      (node (ref "U7") (pin "E17") (pinfunction "DNU_E17") (pintype "passive"))
    )
    (net (code "129") (name "unconnected-(U7L-DNU-PadL9)") (class "Default")
      (node (ref "U7") (pin "L9") (pinfunction "DNU_L9") (pintype "passive"))
    )
    (net (code "130") (name "unconnected-(U7L-NC-PadA17)") (class "Default")
      (node (ref "U7") (pin "A17") (pinfunction "NC_A17") (pintype "passive"))
    )
    (net (code "131") (name "unconnected-(U7L-NC-PadA18)") (class "Default")
      (node (ref "U7") (pin "A18") (pinfunction "NC_A18") (pintype "passive"))
    )
    (net (code "132") (name "unconnected-(U7L-NC-PadA19)") (class "Default")
      (node (ref "U7") (pin "A19") (pinfunction "NC_A19") (pintype "passive"))
    )
    (net (code "133") (name "unconnected-(U7L-NC-PadA20)") (class "Default")
      (node (ref "U7") (pin "A20") (pinfunction "NC_A20") (pintype "passive"))
    )
    (net (code "134") (name "unconnected-(U7L-NC-PadA22)") (class "Default")
      (node (ref "U7") (pin "A22") (pinfunction "NC_A22") (pintype "passive"))
    )
    (net (code "135") (name "unconnected-(U7L-NC-PadB17)") (class "Default")
      (node (ref "U7") (pin "B17") (pinfunction "NC_B17") (pintype "passive"))
    )
    (net (code "136") (name "unconnected-(U7L-NC-PadB18)") (class "Default")
      (node (ref "U7") (pin "B18") (pinfunction "NC_B18") (pintype "passive"))
    )
    (net (code "137") (name "unconnected-(U7L-NC-PadB20)") (class "Default")
      (node (ref "U7") (pin "B20") (pinfunction "NC_B20") (pintype "passive"))
    )
    (net (code "138") (name "unconnected-(U7L-NC-PadB21)") (class "Default")
      (node (ref "U7") (pin "B21") (pinfunction "NC_B21") (pintype "passive"))
    )
    (net (code "139") (name "unconnected-(U7L-NC-PadB22)") (class "Default")
      (node (ref "U7") (pin "B22") (pinfunction "NC_B22") (pintype "passive"))
    )
    (net (code "140") (name "unconnected-(U7L-NC-PadC18)") (class "Default")
      (node (ref "U7") (pin "C18") (pinfunction "NC_C18") (pintype "passive"))
    )
    (net (code "141") (name "unconnected-(U7L-NC-PadC19)") (class "Default")
      (node (ref "U7") (pin "C19") (pinfunction "NC_C19") (pintype "passive"))
    )
    (net (code "142") (name "unconnected-(U7L-NC-PadC20)") (class "Default")
      (node (ref "U7") (pin "C20") (pinfunction "NC_C20") (pintype "passive"))
    )
    (net (code "143") (name "unconnected-(U7L-NC-PadC21)") (class "Default")
      (node (ref "U7") (pin "C21") (pinfunction "NC_C21") (pintype "passive"))
    )
    (net (code "144") (name "unconnected-(U7L-NC-PadD19)") (class "Default")
      (node (ref "U7") (pin "D19") (pinfunction "NC_D19") (pintype "passive"))
    )
    (net (code "145") (name "unconnected-(U7L-NC-PadD21)") (class "Default")
      (node (ref "U7") (pin "D21") (pinfunction "NC_D21") (pintype "passive"))
    )
    (net (code "146") (name "unconnected-(U7L-NC-PadD22)") (class "Default")
      (node (ref "U7") (pin "D22") (pinfunction "NC_D22") (pintype "passive"))
    )
    (net (code "147") (name "unconnected-(U7L-NC-PadE19)") (class "Default")
      (node (ref "U7") (pin "E19") (pinfunction "NC_E19") (pintype "passive"))
    )
    (net (code "148") (name "unconnected-(U7L-NC-PadE20)") (class "Default")
      (node (ref "U7") (pin "E20") (pinfunction "NC_E20") (pintype "passive"))
    )
    (net (code "149") (name "unconnected-(U7L-NC-PadE21)") (class "Default")
      (node (ref "U7") (pin "E21") (pinfunction "NC_E21") (pintype "passive"))
    )
    (net (code "150") (name "unconnected-(U7L-NC-PadE22)") (class "Default")
      (node (ref "U7") (pin "E22") (pinfunction "NC_E22") (pintype "passive"))
    )
    (net (code "151") (name "unconnected-(U7L-NC-PadF18)") (class "Default")
      (node (ref "U7") (pin "F18") (pinfunction "NC_F18") (pintype "passive"))
    )
    (net (code "152") (name "unconnected-(U7L-NC-PadF19)") (class "Default")
      (node (ref "U7") (pin "F19") (pinfunction "NC_F19") (pintype "passive"))
    )
    (net (code "153") (name "unconnected-(U7L-NC-PadF20)") (class "Default")
      (node (ref "U7") (pin "F20") (pinfunction "NC_F20") (pintype "passive"))
    )
    (net (code "154") (name "unconnected-(U7L-NC-PadF22)") (class "Default")
      (node (ref "U7") (pin "F22") (pinfunction "NC_F22") (pintype "passive"))
    )
    (net (code "155") (name "unconnected-(U7L-NC-PadG20)") (class "Default")
      (node (ref "U7") (pin "G20") (pinfunction "NC_G20") (pintype "passive"))
    )
    (net (code "156") (name "unconnected-(U7L-NC-PadG21)") (class "Default")
      (node (ref "U7") (pin "G21") (pinfunction "NC_G21") (pintype "passive"))
    )
    (net (code "157") (name "unconnected-(U7L-NC-PadG22)") (class "Default")
      (node (ref "U7") (pin "G22") (pinfunction "NC_G22") (pintype "passive"))
    )
    (net (code "158") (name "unconnected-(U7L-NC-PadH20)") (class "Default")
      (node (ref "U7") (pin "H20") (pinfunction "NC_H20") (pintype "passive"))
    )
    (net (code "159") (name "unconnected-(U7L-NC-PadH21)") (class "Default")
      (node (ref "U7") (pin "H21") (pinfunction "NC_H21") (pintype "passive"))
    )
    (net (code "160") (name "unconnected-(U7L-NC-PadJ21)") (class "Default")
      (node (ref "U7") (pin "J21") (pinfunction "NC_J21") (pintype "passive"))
    )
    (net (code "161") (name "unconnected-(U7L-NC-PadJ22)") (class "Default")
      (node (ref "U7") (pin "J22") (pinfunction "NC_J22") (pintype "passive"))
    )
    (net (code "162") (name "unconnected-(U7L-NC-PadV11)") (class "Default")
      (node (ref "U7") (pin "V11") (pinfunction "NC_V11") (pintype "passive"))
    )
    (net (code "163") (name "unconnected-(U7L-NC-PadY6)") (class "Default")
      (node (ref "U7") (pin "Y6") (pinfunction "NC_Y6") (pintype "passive"))
    )
  )
)
